# Power.net
KiCad netlist of a schematic drawn in Altium Designer
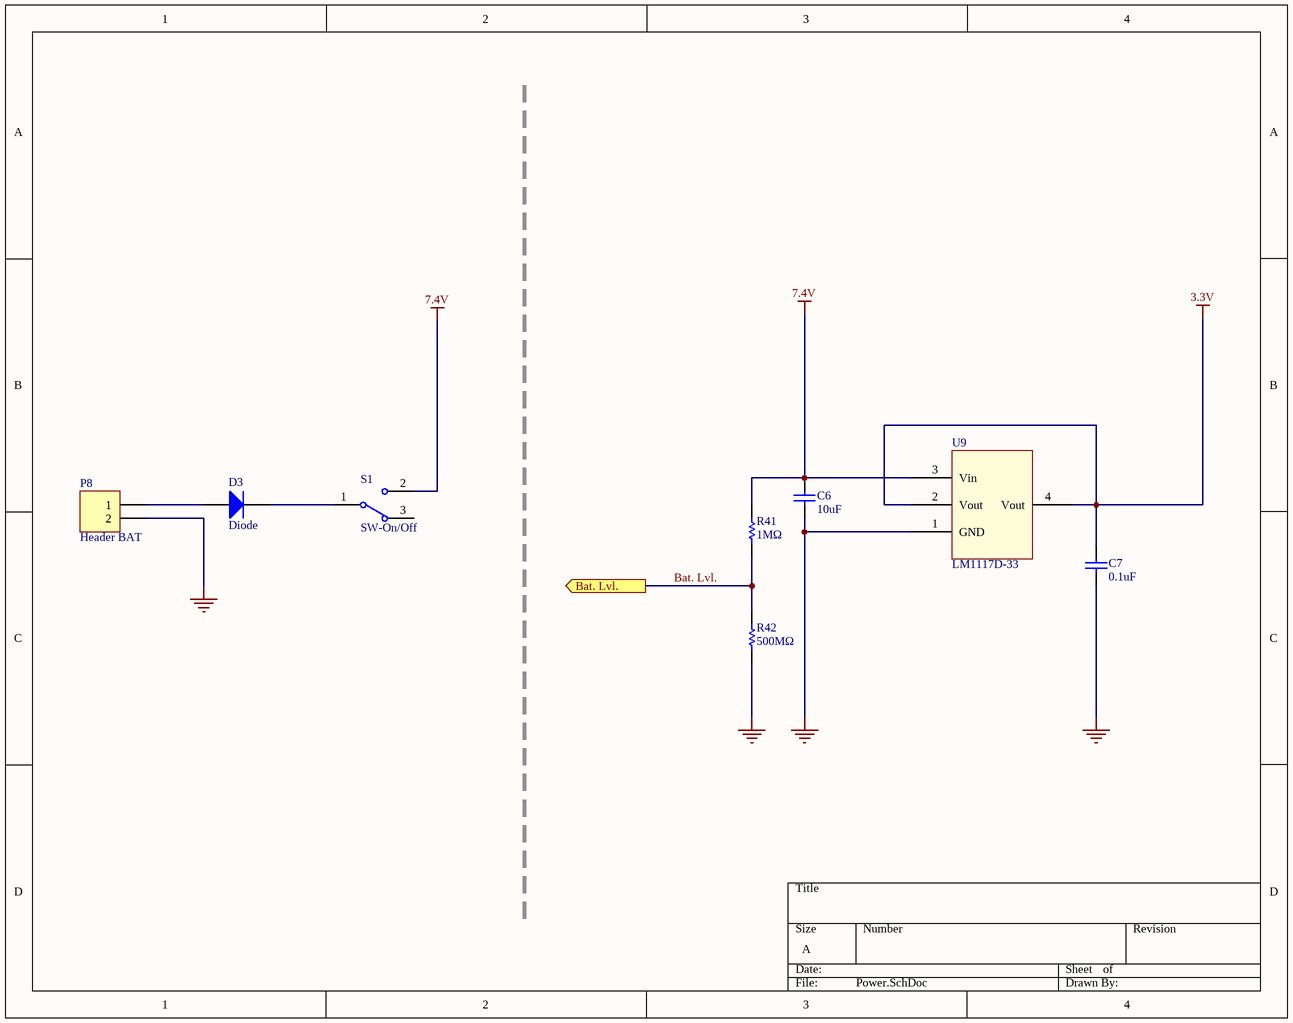
[diagram p0: Power.SchDoc]

(export (version "E")
  (design (tool "Eeschema 10.0.6"))
  (components
    (comp (ref "C6")
      (value "10uF")
      (footprint "C0603")
      (description "Capacitor")
      (fields (field (name "MANUFACTURER") "MURATA") (field (name "PUBLISHER") "Altium Limited"))
      (libsource (lib "Miscellaneous Devices") (part "Cap"))
    )
    (comp (ref "C7")
      (value "0.1uF")
      (footprint "C0603")
      (description "Capacitor")
      (fields (field (name "MANUFACTURER") "MURATA") (field (name "PUBLISHER") "Altium Limited"))
      (libsource (lib "Miscellaneous Devices") (part "Cap"))
    )
    (comp (ref "D3")
      (value "Diode")
      (footprint "DO-219AB")
      (fields (field (name "PUBLISHER") "Altium Limited"))
      (libsource (lib "Miscellaneous Devices") (part "Diode"))
    )
    (comp (ref "P8")
      (value "Header BAT")
      (footprint "BORNIER")
      (description "Header, 2-Pin")
      (fields
        (field (name "MANUFACTURER") "BUCHANAN - TE CONNECTIVITY")
        (field (name "PUBLISHER") "Altium Limited")
      )
      (libsource (lib "Miscellaneous Connectors") (part "Header 2"))
    )
    (comp (ref "R41")
      (value "1MΩ")
      (footprint "R0603")
      (description "Resistor")
      (fields (field (name "MANUFACTURER") "MULTICOMP") (field (name "PUBLISHER") "Altium Limited"))
      (libsource (lib "Miscellaneous Devices") (part "Res1"))
    )
    (comp (ref "R42")
      (value "500MΩ")
      (footprint "R0603")
      (description "Resistor")
      (fields (field (name "MANUFACTURER") "MULTICOMP") (field (name "PUBLISHER") "Altium Limited"))
      (libsource (lib "Miscellaneous Devices") (part "Res1"))
    )
    (comp (ref "S1")
      (value "SW-On/Off")
      (footprint "Switch on/off")
      (description "SPDT Subminiature Toggle Switch, Right Angle Mounting, Vertical Actuation")
      (fields (field (name "MANUFACTURER") "EOZ") (field (name "PUBLISHER") "Altium Limited"))
      (libsource (lib "Miscellaneous Devices") (part "SW-SPDT"))
    )
    (comp (ref "U9")
      (value "LM1117D-33")
      (footprint "VoltReg3.3V")
      (description "Battery")
      (fields (field (name "MANUFACTURER") "TEXAS INSTRUMENTS"))
      (libsource (lib "Electroplant") (part "LM1117D-33"))
    )
  )
  (nets
    (net (code "1") (name "/Bat. Lvl.") (class "Default")
      (node (ref "R41") (pin "1") (pinfunction "1_1") (pintype "passive"))
      (node (ref "R42") (pin "2") (pinfunction "2_2") (pintype "passive"))
    )
    (net (code "2") (name "3.3V") (class "Default")
      (node (ref "C7") (pin "2") (pinfunction "2_2") (pintype "passive"))
      (node (ref "U9") (pin "2") (pinfunction "Vout_2") (pintype "passive"))
      (node (ref "U9") (pin "4") (pinfunction "Vout_4") (pintype "passive"))
    )
    (net (code "3") (name "7.4V") (class "Default")
      (node (ref "C6") (pin "2") (pinfunction "2_2") (pintype "passive"))
      (node (ref "R41") (pin "2") (pinfunction "2_2") (pintype "passive"))
      (node (ref "S1") (pin "2") (pinfunction "2_2") (pintype "passive"))
      (node (ref "U9") (pin "3") (pinfunction "Vin_3") (pintype "passive"))
    )
    (net (code "4") (name "GND") (class "Default")
      (node (ref "C6") (pin "1") (pinfunction "1_1") (pintype "passive"))
      (node (ref "C7") (pin "1") (pinfunction "1_1") (pintype "passive"))
      (node (ref "P8") (pin "2") (pinfunction "2_2") (pintype "passive"))
      (node (ref "R42") (pin "1") (pinfunction "1_1") (pintype "passive"))
      (node (ref "U9") (pin "1") (pinfunction "GND_1") (pintype "passive"))
    )
    (net (code "5") (name "Net-(D3-A)") (class "Default")
      (node (ref "D3") (pin "1") (pinfunction "A_1") (pintype "passive"))
      (node (ref "P8") (pin "1") (pinfunction "1_1") (pintype "passive"))
    )
    (net (code "6") (name "Net-(D3-K)") (class "Default")
      (node (ref "D3") (pin "2") (pinfunction "K_2") (pintype "passive"))
      (node (ref "S1") (pin "1") (pinfunction "1_1") (pintype "passive"))
    )
    (net (code "7") (name "unconnected-(S1-Pad3)") (class "Default")
      (node (ref "S1") (pin "3") (pinfunction "3_3") (pintype "passive"))
    )
  )
)
